# GPS_Shield_v1.net
KiCad netlist of a schematic drawn in EAGLE
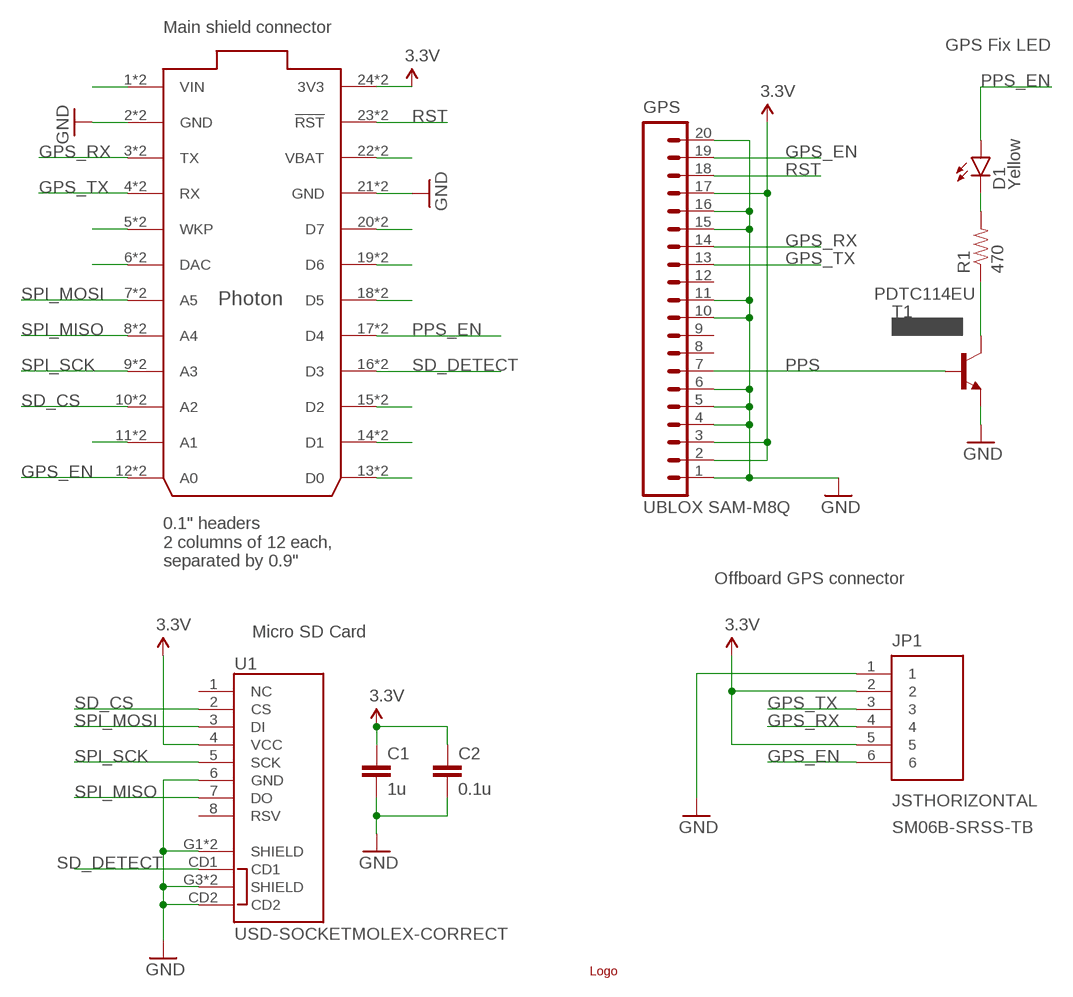
[diagram p0: schematic, sheet 1]

(export (version "E")
  (design (tool "Eeschema 10.0.6"))
  (components
    (comp (ref "C1")
      (value "1u")
      (footprint "eagle-import:0603-CAP")
      (libsource (lib "eagle-import") (part "CAP0603-CAP"))
    )
    (comp (ref "C2")
      (value "0.1u")
      (footprint "eagle-import:0603-CAP")
      (libsource (lib "eagle-import") (part "CAP0603-CAP"))
    )
    (comp (ref "CORE")
      (value "PHOTONWITH_EXTERNAL_HEADERS")
      (footprint "eagle-import:PHOTON_STACKABLE_EXTERNAL")
      (libsource (lib "eagle-import") (part "PHOTONWITH_EXTERNAL_HEADERS"))
    )
    (comp (ref "D1")
      (value "Yellow")
      (footprint "eagle-import:LED-0603")
      (libsource (lib "eagle-import") (part "LED-YELLOW0603"))
    )
    (comp (ref "GPS")
      (value "UBLOX SAM-M8Q")
      (footprint "eagle-import:1X20")
      (libsource (lib "eagle-import") (part "M20"))
    )
    (comp (ref "JP1")
      (value "JSTHORIZONTAL")
      (footprint "eagle-import:JST-6-SMD-HOR-1.0MM")
      (fields (field (name "PARTNO") "SM06B-SRSS-TB"))
      (libsource (lib "eagle-import") (part "JSTHORIZONTAL"))
    )
    (comp (ref "R1")
      (value "470")
      (footprint "eagle-import:0603-RES")
      (libsource (lib "eagle-import") (part "RESISTOR0603-RES"))
    )
    (comp (ref "T1")
      (value "2N2222")
      (footprint "eagle-import:TO18")
      (libsource (lib "eagle-import") (part "2N2222"))
    )
    (comp (ref "U$1")
      (value "LOGO")
      (footprint "eagle-import:CARLOOP")
      (libsource (lib "eagle-import") (part "LOGO"))
    )
    (comp (ref "U1")
      (value "USD-SOCKETMOLEX-CORRECT")
      (footprint "eagle-import:MICRO-SD-MOLEX-CORRECT")
      (libsource (lib "eagle-import") (part "USD-SOCKETMOLEX-CORRECT"))
    )
  )
  (nets
    (net (code "1") (name "/GPS_EN") (class "Default")
      (node (ref "CORE") (pin "12") (pinfunction "A0_12") (pintype "bidirectional"))
      (node (ref "CORE") (pin "@12") (pinfunction "A0_@12") (pintype "bidirectional"))
      (node (ref "GPS") (pin "19") (pinfunction "19_19") (pintype "passive"))
      (node (ref "JP1") (pin "6") (pinfunction "6_6") (pintype "bidirectional"))
    )
    (net (code "2") (name "/GPS_RX") (class "Default")
      (node (ref "CORE") (pin "3") (pinfunction "TX_3") (pintype "bidirectional"))
      (node (ref "CORE") (pin "@3") (pinfunction "TX_@3") (pintype "bidirectional"))
      (node (ref "GPS") (pin "14") (pinfunction "14_14") (pintype "passive"))
      (node (ref "JP1") (pin "4") (pinfunction "4_4") (pintype "bidirectional"))
    )
    (net (code "3") (name "/GPS_TX") (class "Default")
      (node (ref "CORE") (pin "4") (pinfunction "RX_4") (pintype "bidirectional"))
      (node (ref "CORE") (pin "@4") (pinfunction "RX_@4") (pintype "bidirectional"))
      (node (ref "GPS") (pin "13") (pinfunction "13_13") (pintype "passive"))
      (node (ref "JP1") (pin "3") (pinfunction "3_3") (pintype "bidirectional"))
    )
    (net (code "4") (name "/PPS") (class "Default")
      (node (ref "GPS") (pin "7") (pinfunction "7_7") (pintype "passive"))
      (node (ref "T1") (pin "2") (pinfunction "B_2") (pintype "passive"))
    )
    (net (code "5") (name "/PPS_EN") (class "Default")
      (node (ref "CORE") (pin "17") (pinfunction "D4_17") (pintype "bidirectional"))
      (node (ref "CORE") (pin "18") (pinfunction "D5_18") (pintype "bidirectional"))
      (node (ref "CORE") (pin "@17") (pinfunction "D4_@17") (pintype "bidirectional"))
      (node (ref "CORE") (pin "@18") (pinfunction "D5_@18") (pintype "bidirectional"))
      (node (ref "D1") (pin "A") (pinfunction "A_A") (pintype "passive"))
    )
    (net (code "6") (name "/RST") (class "Default")
      (node (ref "CORE") (pin "23") (pinfunction "~{RST}_23") (pintype "bidirectional"))
      (node (ref "CORE") (pin "@23") (pinfunction "~{RST}_@23") (pintype "bidirectional"))
      (node (ref "GPS") (pin "18") (pinfunction "18_18") (pintype "passive"))
    )
    (net (code "7") (name "/SD_CS") (class "Default")
      (node (ref "CORE") (pin "10") (pinfunction "A2_10") (pintype "bidirectional"))
      (node (ref "CORE") (pin "@10") (pinfunction "A2_@10") (pintype "bidirectional"))
      (node (ref "U1") (pin "2") (pinfunction "CS_2") (pintype "bidirectional"))
    )
    (net (code "8") (name "/SD_DETECT") (class "Default")
      (node (ref "CORE") (pin "16") (pinfunction "D3_16") (pintype "bidirectional"))
      (node (ref "CORE") (pin "@16") (pinfunction "D3_@16") (pintype "bidirectional"))
      (node (ref "U1") (pin "CD1") (pinfunction "CD1_CD1") (pintype "bidirectional"))
    )
    (net (code "9") (name "/SPI_MISO") (class "Default")
      (node (ref "CORE") (pin "8") (pinfunction "A4_8") (pintype "bidirectional"))
      (node (ref "CORE") (pin "@8") (pinfunction "A4_@8") (pintype "bidirectional"))
      (node (ref "U1") (pin "7") (pinfunction "DO_7") (pintype "bidirectional"))
    )
    (net (code "10") (name "/SPI_MOSI") (class "Default")
      (node (ref "CORE") (pin "7") (pinfunction "A5_7") (pintype "bidirectional"))
      (node (ref "CORE") (pin "@7") (pinfunction "A5_@7") (pintype "bidirectional"))
      (node (ref "U1") (pin "3") (pinfunction "DI_3") (pintype "bidirectional"))
    )
    (net (code "11") (name "/SPI_SCK") (class "Default")
      (node (ref "CORE") (pin "9") (pinfunction "A3_9") (pintype "bidirectional"))
      (node (ref "CORE") (pin "@9") (pinfunction "A3_@9") (pintype "bidirectional"))
      (node (ref "U1") (pin "5") (pinfunction "SCK_5") (pintype "bidirectional"))
    )
    (net (code "12") (name "3.3V") (class "Default")
      (node (ref "C1") (pin "1") (pinfunction "1_1") (pintype "passive"))
      (node (ref "C2") (pin "1") (pinfunction "1_1") (pintype "passive"))
      (node (ref "CORE") (pin "24") (pinfunction "3V3_24") (pintype "power_in"))
      (node (ref "CORE") (pin "@24") (pinfunction "3V3_@24") (pintype "power_in"))
      (node (ref "GPS") (pin "17") (pinfunction "17_17") (pintype "passive"))
      (node (ref "GPS") (pin "2") (pinfunction "2_2") (pintype "passive"))
      (node (ref "GPS") (pin "3") (pinfunction "3_3") (pintype "passive"))
      (node (ref "JP1") (pin "2") (pinfunction "2_2") (pintype "bidirectional"))
      (node (ref "JP1") (pin "5") (pinfunction "5_5") (pintype "bidirectional"))
      (node (ref "U1") (pin "4") (pinfunction "VCC_4") (pintype "bidirectional"))
    )
    (net (code "13") (name "GND") (class "Default")
      (node (ref "C1") (pin "2") (pinfunction "2_2") (pintype "passive"))
      (node (ref "C2") (pin "2") (pinfunction "2_2") (pintype "passive"))
      (node (ref "CORE") (pin "2") (pinfunction "GND_2") (pintype "power_in"))
      (node (ref "CORE") (pin "21") (pinfunction "GND_21") (pintype "power_in"))
      (node (ref "CORE") (pin "@2") (pinfunction "GND_@2") (pintype "power_in"))
      (node (ref "CORE") (pin "@21") (pinfunction "GND_@21") (pintype "power_in"))
      (node (ref "GPS") (pin "1") (pinfunction "1_1") (pintype "passive"))
      (node (ref "GPS") (pin "10") (pinfunction "10_10") (pintype "passive"))
      (node (ref "GPS") (pin "11") (pinfunction "11_11") (pintype "passive"))
      (node (ref "GPS") (pin "15") (pinfunction "15_15") (pintype "passive"))
      (node (ref "GPS") (pin "16") (pinfunction "16_16") (pintype "passive"))
      (node (ref "GPS") (pin "20") (pinfunction "20_20") (pintype "passive"))
      (node (ref "GPS") (pin "4") (pinfunction "4_4") (pintype "passive"))
      (node (ref "GPS") (pin "5") (pinfunction "5_5") (pintype "passive"))
      (node (ref "GPS") (pin "6") (pinfunction "6_6") (pintype "passive"))
      (node (ref "JP1") (pin "1") (pinfunction "1_1") (pintype "bidirectional"))
      (node (ref "T1") (pin "1") (pinfunction "E_1") (pintype "passive"))
      (node (ref "U1") (pin "6") (pinfunction "GND_6") (pintype "bidirectional"))
      (node (ref "U1") (pin "CD2") (pinfunction "CD2_CD2") (pintype "bidirectional"))
      (node (ref "U1") (pin "G1") (pinfunction "SHIELD_G1") (pintype "bidirectional"))
      (node (ref "U1") (pin "G2") (pinfunction "SHIELD_G2") (pintype "bidirectional"))
      (node (ref "U1") (pin "G3") (pinfunction "SHIELD_G3") (pintype "bidirectional"))
      (node (ref "U1") (pin "G4") (pinfunction "SHIELD_G4") (pintype "bidirectional"))
    )
    (net (code "14") (name "Net-(CORE-A1-Pad11)") (class "Default")
      (node (ref "CORE") (pin "11") (pinfunction "A1_11") (pintype "bidirectional"))
      (node (ref "CORE") (pin "@11") (pinfunction "A1_@11") (pintype "bidirectional"))
    )
    (net (code "15") (name "Net-(CORE-D0-Pad13)") (class "Default")
      (node (ref "CORE") (pin "13") (pinfunction "D0_13") (pintype "bidirectional"))
      (node (ref "CORE") (pin "@13") (pinfunction "D0_@13") (pintype "bidirectional"))
    )
    (net (code "16") (name "Net-(CORE-D1-Pad14)") (class "Default")
      (node (ref "CORE") (pin "14") (pinfunction "D1_14") (pintype "bidirectional"))
      (node (ref "CORE") (pin "@14") (pinfunction "D1_@14") (pintype "bidirectional"))
    )
    (net (code "17") (name "Net-(CORE-D2-Pad15)") (class "Default")
      (node (ref "CORE") (pin "15") (pinfunction "D2_15") (pintype "bidirectional"))
      (node (ref "CORE") (pin "@15") (pinfunction "D2_@15") (pintype "bidirectional"))
    )
    (net (code "18") (name "Net-(CORE-D6-Pad19)") (class "Default")
      (node (ref "CORE") (pin "19") (pinfunction "D6_19") (pintype "bidirectional"))
      (node (ref "CORE") (pin "@19") (pinfunction "D6_@19") (pintype "bidirectional"))
    )
    (net (code "19") (name "Net-(CORE-D7-Pad20)") (class "Default")
      (node (ref "CORE") (pin "20") (pinfunction "D7_20") (pintype "bidirectional"))
      (node (ref "CORE") (pin "@20") (pinfunction "D7_@20") (pintype "bidirectional"))
    )
    (net (code "20") (name "Net-(CORE-DAC-Pad6)") (class "Default")
      (node (ref "CORE") (pin "6") (pinfunction "DAC_6") (pintype "bidirectional"))
      (node (ref "CORE") (pin "@6") (pinfunction "DAC_@6") (pintype "bidirectional"))
    )
    (net (code "21") (name "Net-(CORE-VBAT-Pad22)") (class "Default")
      (node (ref "CORE") (pin "22") (pinfunction "VBAT_22") (pintype "power_in"))
      (node (ref "CORE") (pin "@22") (pinfunction "VBAT_@22") (pintype "power_in"))
    )
    (net (code "22") (name "Net-(CORE-VIN-Pad1)") (class "Default")
      (node (ref "CORE") (pin "1") (pinfunction "VIN_1") (pintype "power_in"))
      (node (ref "CORE") (pin "@1") (pinfunction "VIN_@1") (pintype "power_in"))
    )
    (net (code "23") (name "Net-(CORE-WKP-Pad5)") (class "Default")
      (node (ref "CORE") (pin "5") (pinfunction "WKP_5") (pintype "bidirectional"))
      (node (ref "CORE") (pin "@5") (pinfunction "WKP_@5") (pintype "bidirectional"))
    )
    (net (code "24") (name "Net-(D1-PadC)") (class "Default")
      (node (ref "D1") (pin "C") (pinfunction "C_C") (pintype "passive"))
      (node (ref "R1") (pin "2") (pinfunction "2_2") (pintype "passive"))
    )
    (net (code "25") (name "Net-(T1-C)") (class "Default")
      (node (ref "R1") (pin "1") (pinfunction "1_1") (pintype "passive"))
      (node (ref "T1") (pin "3") (pinfunction "C_3") (pintype "passive"))
    )
    (net (code "26") (name "unconnected-(GPS-Pad8)") (class "Default")
      (node (ref "GPS") (pin "8") (pinfunction "8_8") (pintype "passive"))
    )
    (net (code "27") (name "unconnected-(GPS-Pad9)") (class "Default")
      (node (ref "GPS") (pin "9") (pinfunction "9_9") (pintype "passive"))
    )
    (net (code "28") (name "unconnected-(GPS-Pad12)") (class "Default")
      (node (ref "GPS") (pin "12") (pinfunction "12_12") (pintype "passive"))
    )
    (net (code "29") (name "unconnected-(U1-NC-Pad1)") (class "Default")
      (node (ref "U1") (pin "1") (pinfunction "NC_1") (pintype "bidirectional"))
    )
    (net (code "30") (name "unconnected-(U1-RSV-Pad8)") (class "Default")
      (node (ref "U1") (pin "8") (pinfunction "RSV_8") (pintype "bidirectional"))
    )
  )
)
